# ngh-main.net
KiCad netlist of a schematic drawn in Altium Designer
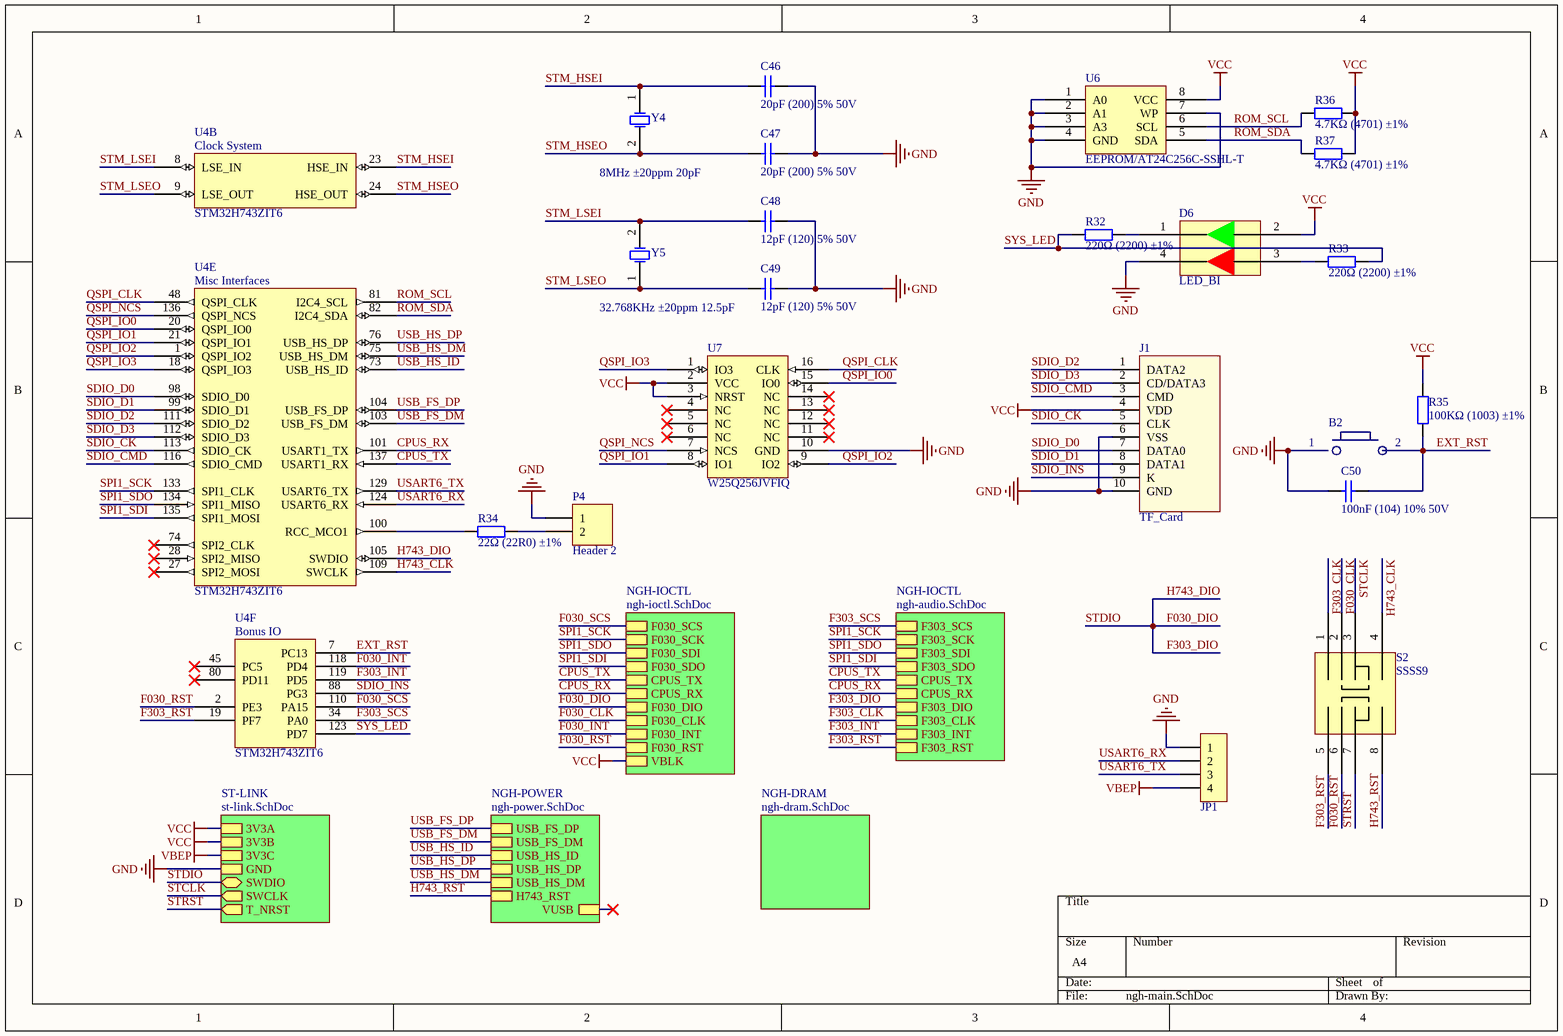
[diagram p0: ngh-main.SchDoc]

(export (version "E")
  (design (tool "Eeschema 10.0.6"))
  (components
    (comp (ref "B2")
      (value "B1")
      (footprint "MetalButton")
      (libsource (lib "MetalButton") (part "MetalButton"))
    )
    (comp (ref "C46")
      (value "20pF (200) 5% 50V")
      (footprint "0603_C")
      (description "贴片电容")
      (libsource (lib "Miscellaneous Devices LC") (part "0603 20pF (200) 5% 50V"))
    )
    (comp (ref "C47")
      (value "20pF (200) 5% 50V")
      (footprint "0603_C")
      (description "贴片电容")
      (libsource (lib "Miscellaneous Devices LC") (part "0603 20pF (200) 5% 50V"))
    )
    (comp (ref "C48")
      (value "12pF (120) 5% 50V")
      (footprint "0603_C")
      (description "贴片电容")
      (libsource (lib "Miscellaneous Devices LC") (part "0603 12pF (120) 5% 50V"))
    )
    (comp (ref "C49")
      (value "12pF (120) 5% 50V")
      (footprint "0603_C")
      (description "贴片电容")
      (libsource (lib "Miscellaneous Devices LC") (part "0603 12pF (120) 5% 50V"))
    )
    (comp (ref "C50")
      (value "100nF (104) 10% 50V")
      (footprint "0603_C")
      (description "贴片电容")
      (libsource (lib "Miscellaneous Devices LC") (part "0603 100nF (104) 10% 50V"))
    )
    (comp (ref "D6") (value "LED_BI") (footprint "LED_BI") (libsource (lib "ngh-util") (part "LED_BI")))
    (comp (ref "J1")
      (value "TF_Card")
      (footprint "Micro SD")
      (description "TF卡座")
      (fields (field (name "版权归属") "源创客"))
      (libsource (lib "4.1   - 接口类") (part "TF_Card"))
    )
    (comp (ref "JP1")
      (value "HDR-1X4")
      (footprint "HDR2.54-WS-4P")
      (description "4P接插件")
      (fields (field (name "版权归属") "源创客"))
      (libsource (lib "4.5   - 接插件-脚距2.54") (part "Header 4"))
    )
    (comp (ref "P4")
      (value "Header 2")
      (footprint "HDR1X2")
      (description "Header, 2-Pin")
      (fields (field (name "PUBLISHER") "Altium Limited"))
      (libsource (lib "Miscellaneous Connectors") (part "Header 2"))
    )
    (comp (ref "R32")
      (value "220Ω (2200) ±1%")
      (footprint "0603_R")
      (description "贴片电阻")
      (libsource (lib "Miscellaneous Devices LC") (part "0603 220Ω (2200) 1%"))
    )
    (comp (ref "R33")
      (value "220Ω (2200) ±1%")
      (footprint "0603_R")
      (description "贴片电阻")
      (libsource (lib "Miscellaneous Devices LC") (part "0603 220Ω (2200) 1%"))
    )
    (comp (ref "R34")
      (value "22Ω (22R0) ±1%")
      (footprint "0603_R")
      (description "贴片电阻")
      (libsource (lib "Miscellaneous Devices LC") (part "0603 22Ω (22R0) 1%"))
    )
    (comp (ref "R35")
      (value "100KΩ (1003) ±1%")
      (footprint "0603_R")
      (description "贴片电阻")
      (libsource (lib "Miscellaneous Devices LC") (part "0603 100KΩ (1003) 1%"))
    )
    (comp (ref "R36")
      (value "4.7KΩ (4701) ±1%")
      (footprint "0603_R")
      (description "贴片电阻")
      (libsource (lib "Miscellaneous Devices LC") (part "0603 4.7KΩ (4701) 1%"))
    )
    (comp (ref "R37")
      (value "4.7KΩ (4701) ±1%")
      (footprint "0603_R")
      (description "贴片电阻")
      (libsource (lib "Miscellaneous Devices LC") (part "0603 4.7KΩ (4701) 1%"))
    )
    (comp (ref "S2") (value "SSSS9") (footprint "SSSS9_5mm_H") (libsource (lib "ngh-util") (part "SSSS9")))
    (comp (ref "U4")
      (value "STM32H743ZIT6")
      (footprint "LQFP-144_20x20")
      (libsource (lib "STM32H743ZI") (part "STM32H743ZIT6"))
    )
    (comp (ref "U6")
      (value "EEPROM/AT24C256C-SSHL-T")
      (footprint "SOIC-8_150mil")
      (description "EEPROM")
      (libsource (lib "Miscellaneous Devices LC") (part "EEPROM/AT24C256C-SSHL-T_[C6482]"))
    )
    (comp (ref "U7")
      (value "W25Q256JVFIQ")
      (footprint "SOIC-16_300mil")
      (libsource (lib "W25Q256JVFIQ") (part "W25Q256JVFIQ"))
    )
    (comp (ref "Y4")
      (value "8MHz ±20ppm 20pF")
      (footprint "SMD-5032_2P")
      (description "贴片晶振")
      (libsource (lib "Miscellaneous Devices LC") (part "SMD-5032_2P 8MHz 20ppm 20pF"))
    )
    (comp (ref "Y5")
      (value "32.768KHz ±20ppm 12.5pF")
      (footprint "SMD-3215_2P FC - 135")
      (description "贴片晶振")
      (libsource (lib "Miscellaneous Devices LC") (part "SMD-3215_2P 32.768KHz 20ppm 12.5pF"))
    )
  )
  (nets
    (net (code "1") (name "/CPUS_RX") (class "Default")
      (node (ref "U4") (pin "101") (pinfunction "USART1_TX_101") (pintype "output"))
    )
    (net (code "2") (name "/CPUS_TX") (class "Default")
      (node (ref "U4") (pin "137") (pinfunction "USART1_RX_137") (pintype "input"))
    )
    (net (code "3") (name "/EXT_RST") (class "Default")
      (node (ref "B2") (pin "2") (pinfunction "2_2") (pintype "passive"))
      (node (ref "C50") (pin "2") (pinfunction "2_2") (pintype "passive"))
      (node (ref "R35") (pin "1") (pinfunction "1_1") (pintype "passive"))
      (node (ref "U4") (pin "7") (pinfunction "PC13_7") (pintype "passive"))
    )
    (net (code "4") (name "/F030_CLK") (class "Default")
      (node (ref "S2") (pin "2") (pinfunction "2_2") (pintype "passive"))
    )
    (net (code "5") (name "/F030_DIO") (class "Default")
      (node (ref "U4") (pin "105") (pinfunction "SWDIO_105") (pintype "bidirectional"))
    )
    (net (code "6") (name "/F030_INT") (class "Default")
      (node (ref "U4") (pin "118") (pinfunction "PD4_118") (pintype "passive"))
    )
    (net (code "7") (name "/F030_RST") (class "Default")
      (node (ref "S2") (pin "6") (pinfunction "6_6") (pintype "passive"))
      (node (ref "U4") (pin "2") (pinfunction "PE3_2") (pintype "passive"))
    )
    (net (code "8") (name "/F030_SCS") (class "Default")
      (node (ref "U4") (pin "110") (pinfunction "PA15_110") (pintype "passive"))
    )
    (net (code "9") (name "/F303_CLK") (class "Default")
      (node (ref "S2") (pin "1") (pinfunction "1_1") (pintype "passive"))
    )
    (net (code "10") (name "/F303_INT") (class "Default")
      (node (ref "U4") (pin "119") (pinfunction "PD5_119") (pintype "passive"))
    )
    (net (code "11") (name "/F303_RST") (class "Default")
      (node (ref "S2") (pin "5") (pinfunction "5_5") (pintype "passive"))
      (node (ref "U4") (pin "19") (pinfunction "PF7_19") (pintype "passive"))
    )
    (net (code "12") (name "/F303_SCS") (class "Default")
      (node (ref "U4") (pin "34") (pinfunction "PA0_34") (pintype "passive"))
    )
    (net (code "13") (name "/H743_CLK") (class "Default")
      (node (ref "S2") (pin "4") (pinfunction "4_4") (pintype "passive"))
      (node (ref "U4") (pin "109") (pinfunction "SWCLK_109") (pintype "output"))
    )
    (net (code "14") (name "/H743_RST") (class "Default")
      (node (ref "S2") (pin "8") (pinfunction "8_8") (pintype "passive"))
    )
    (net (code "15") (name "/QSPI_CLK") (class "Default")
      (node (ref "U4") (pin "48") (pinfunction "QSPI_CLK_48") (pintype "output"))
      (node (ref "U7") (pin "16") (pinfunction "CLK_16") (pintype "input"))
    )
    (net (code "16") (name "/QSPI_IO0") (class "Default")
      (node (ref "U4") (pin "20") (pinfunction "QSPI_IO0_20") (pintype "bidirectional"))
      (node (ref "U7") (pin "15") (pinfunction "IO0_15") (pintype "bidirectional"))
    )
    (net (code "17") (name "/QSPI_IO1") (class "Default")
      (node (ref "U4") (pin "21") (pinfunction "QSPI_IO1_21") (pintype "bidirectional"))
      (node (ref "U7") (pin "8") (pinfunction "IO1_8") (pintype "bidirectional"))
    )
    (net (code "18") (name "/QSPI_IO2") (class "Default")
      (node (ref "U4") (pin "1") (pinfunction "QSPI_IO2_1") (pintype "bidirectional"))
      (node (ref "U7") (pin "9") (pinfunction "IO2_9") (pintype "bidirectional"))
    )
    (net (code "19") (name "/QSPI_IO3") (class "Default")
      (node (ref "U4") (pin "18") (pinfunction "QSPI_IO3_18") (pintype "bidirectional"))
      (node (ref "U7") (pin "1") (pinfunction "IO3_1") (pintype "bidirectional"))
    )
    (net (code "20") (name "/QSPI_NCS") (class "Default")
      (node (ref "U4") (pin "136") (pinfunction "QSPI_NCS_136") (pintype "output"))
      (node (ref "U7") (pin "7") (pinfunction "NCS_7") (pintype "input"))
    )
    (net (code "21") (name "/ROM_SCL") (class "Default")
      (node (ref "R36") (pin "2") (pinfunction "2_2") (pintype "passive"))
      (node (ref "U4") (pin "81") (pinfunction "I2C4_SCL_81") (pintype "output"))
      (node (ref "U6") (pin "6") (pinfunction "SCL_6") (pintype "passive"))
    )
    (net (code "22") (name "/ROM_SDA") (class "Default")
      (node (ref "R37") (pin "2") (pinfunction "2_2") (pintype "passive"))
      (node (ref "U4") (pin "82") (pinfunction "I2C4_SDA_82") (pintype "bidirectional"))
      (node (ref "U6") (pin "5") (pinfunction "SDA_5") (pintype "passive"))
    )
    (net (code "23") (name "/SDIO_CK") (class "Default")
      (node (ref "J1") (pin "5") (pinfunction "CLK_5") (pintype "passive"))
      (node (ref "U4") (pin "113") (pinfunction "SDIO_CK_113") (pintype "output"))
    )
    (net (code "24") (name "/SDIO_CMD") (class "Default")
      (node (ref "J1") (pin "3") (pinfunction "CMD_3") (pintype "passive"))
      (node (ref "U4") (pin "116") (pinfunction "SDIO_CMD_116") (pintype "output"))
    )
    (net (code "25") (name "/SDIO_D0") (class "Default")
      (node (ref "J1") (pin "7") (pinfunction "DATA0_7") (pintype "passive"))
      (node (ref "U4") (pin "98") (pinfunction "SDIO_D0_98") (pintype "bidirectional"))
    )
    (net (code "26") (name "/SDIO_D1") (class "Default")
      (node (ref "J1") (pin "8") (pinfunction "DATA1_8") (pintype "passive"))
      (node (ref "U4") (pin "99") (pinfunction "SDIO_D1_99") (pintype "bidirectional"))
    )
    (net (code "27") (name "/SDIO_D2") (class "Default")
      (node (ref "J1") (pin "1") (pinfunction "DATA2_1") (pintype "passive"))
      (node (ref "U4") (pin "111") (pinfunction "SDIO_D2_111") (pintype "bidirectional"))
    )
    (net (code "28") (name "/SDIO_D3") (class "Default")
      (node (ref "J1") (pin "2") (pinfunction "CD/DATA3_2") (pintype "passive"))
      (node (ref "U4") (pin "112") (pinfunction "SDIO_D3_112") (pintype "bidirectional"))
    )
    (net (code "29") (name "/SDIO_INS") (class "Default")
      (node (ref "J1") (pin "9") (pinfunction "K_9") (pintype "passive"))
      (node (ref "U4") (pin "88") (pinfunction "PG3_88") (pintype "passive"))
    )
    (net (code "30") (name "/SPI1_SCK") (class "Default")
      (node (ref "U4") (pin "133") (pinfunction "SPI1_CLK_133") (pintype "output"))
    )
    (net (code "31") (name "/SPI1_SDI") (class "Default")
      (node (ref "U4") (pin "135") (pinfunction "SPI1_MOSI_135") (pintype "output"))
    )
    (net (code "32") (name "/SPI1_SDO") (class "Default")
      (node (ref "U4") (pin "134") (pinfunction "SPI1_MISO_134") (pintype "input"))
    )
    (net (code "33") (name "/STCLK") (class "Default")
      (node (ref "S2") (pin "3") (pinfunction "3_3") (pintype "passive"))
    )
    (net (code "34") (name "/STM_HSEI") (class "Default")
      (node (ref "C46") (pin "1") (pinfunction "1_1") (pintype "passive"))
      (node (ref "U4") (pin "23") (pinfunction "HSE_IN_23") (pintype "bidirectional"))
      (node (ref "Y4") (pin "1") (pinfunction "OSC1_1") (pintype "passive"))
    )
    (net (code "35") (name "/STM_HSEO") (class "Default")
      (node (ref "C47") (pin "1") (pinfunction "1_1") (pintype "passive"))
      (node (ref "U4") (pin "24") (pinfunction "HSE_OUT_24") (pintype "bidirectional"))
      (node (ref "Y4") (pin "2") (pinfunction "OSC2_2") (pintype "passive"))
    )
    (net (code "36") (name "/STM_LSEI") (class "Default")
      (node (ref "C48") (pin "1") (pinfunction "1_1") (pintype "passive"))
      (node (ref "U4") (pin "8") (pinfunction "LSE_IN_8") (pintype "bidirectional"))
      (node (ref "Y5") (pin "2") (pinfunction "OSC2_2") (pintype "passive"))
    )
    (net (code "37") (name "/STM_LSEO") (class "Default")
      (node (ref "C49") (pin "1") (pinfunction "1_1") (pintype "passive"))
      (node (ref "U4") (pin "9") (pinfunction "LSE_OUT_9") (pintype "bidirectional"))
      (node (ref "Y5") (pin "1") (pinfunction "OSC1_1") (pintype "passive"))
    )
    (net (code "38") (name "/STRST") (class "Default")
      (node (ref "S2") (pin "7") (pinfunction "7_7") (pintype "passive"))
    )
    (net (code "39") (name "/SYS_LED") (class "Default")
      (node (ref "R32") (pin "1") (pinfunction "1_1") (pintype "passive"))
      (node (ref "R33") (pin "2") (pinfunction "2_2") (pintype "passive"))
      (node (ref "U4") (pin "123") (pinfunction "PD7_123") (pintype "passive"))
    )
    (net (code "40") (name "/USART6_RX") (class "Default")
      (node (ref "JP1") (pin "2") (pinfunction "2_2") (pintype "passive"))
      (node (ref "U4") (pin "124") (pinfunction "USART6_RX_124") (pintype "input"))
    )
    (net (code "41") (name "/USART6_TX") (class "Default")
      (node (ref "JP1") (pin "3") (pinfunction "3_3") (pintype "passive"))
      (node (ref "U4") (pin "129") (pinfunction "USART6_TX_129") (pintype "output"))
    )
    (net (code "42") (name "/USB_FS_DM") (class "Default")
      (node (ref "U4") (pin "103") (pinfunction "USB_FS_DM_103") (pintype "bidirectional"))
    )
    (net (code "43") (name "/USB_FS_DP") (class "Default")
      (node (ref "U4") (pin "104") (pinfunction "USB_FS_DP_104") (pintype "bidirectional"))
    )
    (net (code "44") (name "/USB_HS_DM") (class "Default")
      (node (ref "U4") (pin "75") (pinfunction "USB_HS_DM_75") (pintype "bidirectional"))
    )
    (net (code "45") (name "/USB_HS_DP") (class "Default")
      (node (ref "U4") (pin "76") (pinfunction "USB_HS_DP_76") (pintype "bidirectional"))
    )
    (net (code "46") (name "/USB_HS_ID") (class "Default")
      (node (ref "U4") (pin "73") (pinfunction "USB_HS_ID_73") (pintype "bidirectional"))
    )
    (net (code "48") (name "GND") (class "Default")
      (node (ref "B2") (pin "1") (pinfunction "1_1") (pintype "passive"))
      (node (ref "C46") (pin "2") (pinfunction "2_2") (pintype "passive"))
      (node (ref "C47") (pin "2") (pinfunction "2_2") (pintype "passive"))
      (node (ref "C48") (pin "2") (pinfunction "2_2") (pintype "passive"))
      (node (ref "C49") (pin "2") (pinfunction "2_2") (pintype "passive"))
      (node (ref "C50") (pin "1") (pinfunction "1_1") (pintype "passive"))
      (node (ref "D6") (pin "4") (pinfunction "4_4") (pintype "passive"))
      (node (ref "J1") (pin "10") (pinfunction "GND_10") (pintype "passive"))
      (node (ref "J1") (pin "6") (pinfunction "VSS_6") (pintype "passive"))
      (node (ref "JP1") (pin "1") (pinfunction "1_1") (pintype "passive"))
      (node (ref "P4") (pin "1") (pinfunction "1_1") (pintype "passive"))
      (node (ref "U6") (pin "1") (pinfunction "A0_1") (pintype "passive"))
      (node (ref "U6") (pin "2") (pinfunction "A1_2") (pintype "passive"))
      (node (ref "U6") (pin "3") (pinfunction "A3_3") (pintype "passive"))
      (node (ref "U6") (pin "4") (pinfunction "GND_4") (pintype "passive"))
      (node (ref "U6") (pin "7") (pinfunction "WP_7") (pintype "passive"))
      (node (ref "U7") (pin "10") (pinfunction "GND_10") (pintype "power_in"))
    )
    (net (code "49") (name "Net-(D6-Pad1)") (class "Default")
      (node (ref "D6") (pin "1") (pinfunction "1_1") (pintype "passive"))
      (node (ref "R32") (pin "2") (pinfunction "2_2") (pintype "passive"))
    )
    (net (code "50") (name "Net-(D6-Pad3)") (class "Default")
      (node (ref "D6") (pin "3") (pinfunction "3_3") (pintype "passive"))
      (node (ref "R33") (pin "1") (pinfunction "1_1") (pintype "passive"))
    )
    (net (code "51") (name "Net-(P4-Pad2)") (class "Default")
      (node (ref "P4") (pin "2") (pinfunction "2_2") (pintype "passive"))
      (node (ref "R34") (pin "2") (pinfunction "2_2") (pintype "passive"))
    )
    (net (code "52") (name "Net-(U4E-RCC_MCO1)") (class "Default")
      (node (ref "R34") (pin "1") (pinfunction "1_1") (pintype "passive"))
      (node (ref "U4") (pin "100") (pinfunction "RCC_MCO1_100") (pintype "output"))
    )
    (net (code "53") (name "VBEP") (class "Default")
      (node (ref "JP1") (pin "4") (pinfunction "4_4") (pintype "passive"))
    )
    (net (code "54") (name "VCC") (class "Default")
      (node (ref "D6") (pin "2") (pinfunction "2_2") (pintype "passive"))
      (node (ref "J1") (pin "4") (pinfunction "VDD_4") (pintype "passive"))
      (node (ref "R35") (pin "2") (pinfunction "2_2") (pintype "passive"))
      (node (ref "R36") (pin "1") (pinfunction "1_1") (pintype "passive"))
      (node (ref "R37") (pin "1") (pinfunction "1_1") (pintype "passive"))
      (node (ref "U6") (pin "8") (pinfunction "VCC_8") (pintype "passive"))
      (node (ref "U7") (pin "2") (pinfunction "VCC_2") (pintype "power_in"))
      (node (ref "U7") (pin "3") (pinfunction "NRST_3") (pintype "input"))
    )
    (net (code "55") (name "unconnected-(U4E-SPI2_CLK-Pad74)") (class "Default")
      (node (ref "U4") (pin "74") (pinfunction "SPI2_CLK_74") (pintype "output+no_connect"))
    )
    (net (code "56") (name "unconnected-(U4E-SPI2_MISO-Pad28)") (class "Default")
      (node (ref "U4") (pin "28") (pinfunction "SPI2_MISO_28") (pintype "input+no_connect"))
    )
    (net (code "57") (name "unconnected-(U4E-SPI2_MOSI-Pad27)") (class "Default")
      (node (ref "U4") (pin "27") (pinfunction "SPI2_MOSI_27") (pintype "output+no_connect"))
    )
    (net (code "58") (name "unconnected-(U4F-PC5-Pad45)") (class "Default")
      (node (ref "U4") (pin "45") (pinfunction "PC5_45") (pintype "passive+no_connect"))
    )
    (net (code "59") (name "unconnected-(U4F-PD11-Pad80)") (class "Default")
      (node (ref "U4") (pin "80") (pinfunction "PD11_80") (pintype "passive+no_connect"))
    )
    (net (code "60") (name "unconnected-(U7-NC-Pad4)") (class "Default")
      (node (ref "U7") (pin "4") (pinfunction "NC_4") (pintype "passive+no_connect"))
    )
    (net (code "61") (name "unconnected-(U7-NC-Pad5)") (class "Default")
      (node (ref "U7") (pin "5") (pinfunction "NC_5") (pintype "passive+no_connect"))
    )
    (net (code "62") (name "unconnected-(U7-NC-Pad6)") (class "Default")
      (node (ref "U7") (pin "6") (pinfunction "NC_6") (pintype "passive+no_connect"))
    )
    (net (code "63") (name "unconnected-(U7-NC-Pad11)") (class "Default")
      (node (ref "U7") (pin "11") (pinfunction "NC_11") (pintype "passive+no_connect"))
    )
    (net (code "64") (name "unconnected-(U7-NC-Pad12)") (class "Default")
      (node (ref "U7") (pin "12") (pinfunction "NC_12") (pintype "passive+no_connect"))
    )
    (net (code "65") (name "unconnected-(U7-NC-Pad13)") (class "Default")
      (node (ref "U7") (pin "13") (pinfunction "NC_13") (pintype "passive+no_connect"))
    )
    (net (code "66") (name "unconnected-(U7-NC-Pad14)") (class "Default")
      (node (ref "U7") (pin "14") (pinfunction "NC_14") (pintype "passive+no_connect"))
    )
  )
)
